# esp32-wroom-32.net
KiCad netlist of a schematic drawn in Altium Designer
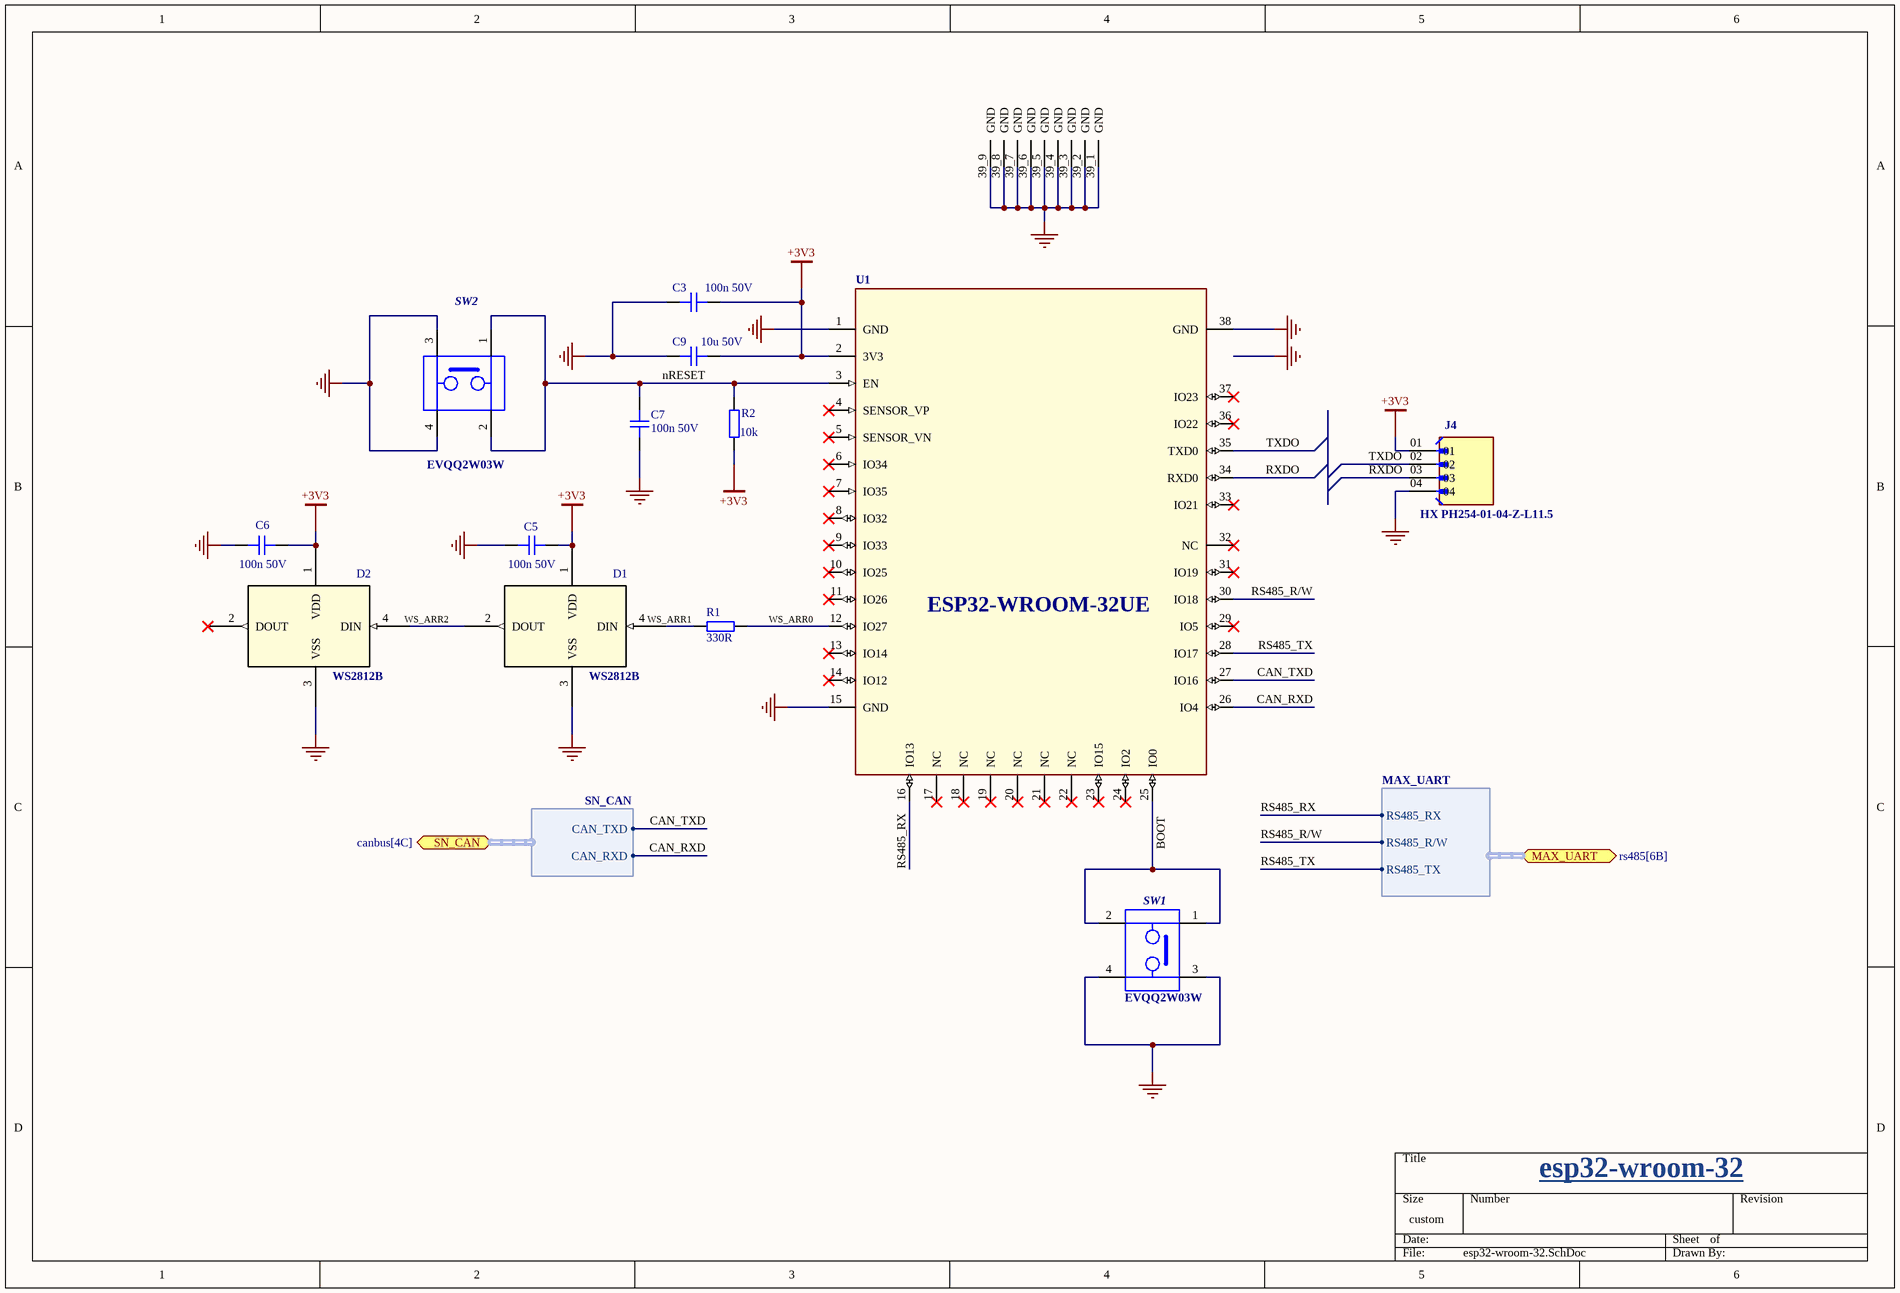
[diagram p0: esp32-wroom-32.SchDoc]

(export (version "E")
  (design (tool "Eeschema 10.0.6"))
  (components
    (comp (ref "C3")
      (value "100n 50V")
      (footprint "CAP_0603")
      (description "Capacitor SMD 0603")
      (libsource (lib "Sch_Lib") (part "CAP_0603"))
    )
    (comp (ref "C5")
      (value "100n 50V")
      (footprint "CAP_0603")
      (description "Capacitor SMD 0603")
      (libsource (lib "Sch_Lib") (part "CAP_0603"))
    )
    (comp (ref "C6")
      (value "100n 50V")
      (footprint "CAP_0603")
      (description "Capacitor SMD 0603")
      (libsource (lib "Sch_Lib") (part "CAP_0603"))
    )
    (comp (ref "C7")
      (value "100n 50V")
      (footprint "CAP_0805")
      (description "Capacitor SMD 0805")
      (libsource (lib "Sch_Lib") (part "CAP_0805"))
    )
    (comp (ref "C9")
      (value "10u 50V")
      (footprint "CAP_0603")
      (description "Capacitor SMD 0603")
      (libsource (lib "Sch_Lib") (part "CAP_0603"))
    )
    (comp (ref "D1")
      (value "WS2812B")
      (footprint "WS2812B_WDS")
      (description "Description")
      (fields (field (name "COPYRIGHT") "Copyright (C) 2026 Ultra Librarian. All rights reserved."))
      (libsource (lib "Sch_Lib") (part "WS2812B"))
    )
    (comp (ref "D2")
      (value "WS2812B")
      (footprint "WS2812B_WDS")
      (description "Description")
      (fields (field (name "COPYRIGHT") "Copyright (C) 2026 Ultra Librarian. All rights reserved."))
      (libsource (lib "Sch_Lib") (part "WS2812B"))
    )
    (comp (ref "J4")
      (value "HX PH254-01-04-Z-L11.5")
      (footprint "SAMTEC_TSW-104-08-T-S-LL")
      (fields (field (name "MF") "Samtec") (field (name "MP") "TSW-104-08-T-S-LL"))
      (libsource (lib "Sch_Lib") (part "4PIN_TSW-104-08-T-S-LL"))
    )
    (comp (ref "R1")
      (value "330R")
      (footprint "RES_0805")
      (description "Resistor SMD 0805")
      (libsource (lib "Sch_Lib") (part "RES_0805"))
    )
    (comp (ref "R2")
      (value "10k")
      (footprint "RES_0805")
      (description "Resistor SMD 0805")
      (libsource (lib "Sch_Lib") (part "RES_0805"))
    )
    (comp (ref "SW1")
      (value "EVQQ2W03W")
      (footprint "EVQQ2W03W")
      (description "White Push Plate Tactile Switch, SPST-NO 20 mA 3.1mm")
      (fields (field (name "MF") "Panasonic"))
      (libsource (lib "Sch_Lib") (part "EVQQ2W03W"))
    )
    (comp (ref "SW2")
      (value "EVQQ2W03W")
      (footprint "EVQQ2W03W")
      (description "White Push Plate Tactile Switch, SPST-NO 20 mA 3.1mm")
      (fields (field (name "MF") "Panasonic"))
      (libsource (lib "Sch_Lib") (part "EVQQ2W03W"))
    )
    (comp (ref "U1")
      (value "ESP32-WROOM-32UE")
      (footprint "MODULE_ESP32-WROOM-32UE(M113EH6400UH3Q0)")
      (fields (field (name "MF") "Espressif Systems") (field (name "MP") "ESP32-WROOM-32UE(M113EH6400UH3Q0)"))
      (libsource (lib "Sch_Lib") (part "ESP32-WROOM-32UE(M113EH6400UH3Q0)"))
    )
  )
  (nets
    (net (code "3") (name "+3V3") (class "Default")
      (node (ref "C3") (pin "2") (pinfunction "2_2") (pintype "passive"))
      (node (ref "C5") (pin "2") (pinfunction "2_2") (pintype "passive"))
      (node (ref "C6") (pin "2") (pinfunction "2_2") (pintype "passive"))
      (node (ref "C9") (pin "2") (pinfunction "2_2") (pintype "passive"))
      (node (ref "D1") (pin "1") (pinfunction "VDD_1") (pintype "power_in"))
      (node (ref "D2") (pin "1") (pinfunction "VDD_1") (pintype "power_in"))
      (node (ref "J4") (pin "01") (pinfunction "01_01") (pintype "passive"))
      (node (ref "R2") (pin "1") (pinfunction "1_1") (pintype "passive"))
      (node (ref "U1") (pin "2") (pinfunction "3V3_2") (pintype "power_in"))
    )
    (net (code "4") (name "/BOOT") (class "Default")
      (node (ref "SW1") (pin "1") (pinfunction "1_1") (pintype "passive"))
      (node (ref "SW1") (pin "2") (pinfunction "2_2") (pintype "passive"))
      (node (ref "U1") (pin "25") (pinfunction "IO0_25") (pintype "bidirectional"))
    )
    (net (code "5") (name "/CAN_RXD") (class "Default")
      (node (ref "U1") (pin "26") (pinfunction "IO4_26") (pintype "bidirectional"))
    )
    (net (code "6") (name "/CAN_TXD") (class "Default")
      (node (ref "U1") (pin "27") (pinfunction "IO16_27") (pintype "bidirectional"))
    )
    (net (code "7") (name "/RS485_RX") (class "Default")
      (node (ref "U1") (pin "16") (pinfunction "IO13_16") (pintype "bidirectional"))
    )
    (net (code "8") (name "/RS485_R{slash}W") (class "Default")
      (node (ref "U1") (pin "30") (pinfunction "IO18_30") (pintype "bidirectional"))
    )
    (net (code "9") (name "/RS485_TX") (class "Default")
      (node (ref "U1") (pin "28") (pinfunction "IO17_28") (pintype "bidirectional"))
    )
    (net (code "10") (name "/RXDO") (class "Default")
      (node (ref "J4") (pin "03") (pinfunction "03_03") (pintype "passive"))
      (node (ref "U1") (pin "34") (pinfunction "RXD0_34") (pintype "bidirectional"))
    )
    (net (code "11") (name "/TXDO") (class "Default")
      (node (ref "J4") (pin "02") (pinfunction "02_02") (pintype "passive"))
      (node (ref "U1") (pin "35") (pinfunction "TXD0_35") (pintype "bidirectional"))
    )
    (net (code "12") (name "/WS_ARR0") (class "Default")
      (node (ref "R1") (pin "1") (pinfunction "1_1") (pintype "passive"))
      (node (ref "U1") (pin "12") (pinfunction "IO27_12") (pintype "bidirectional"))
    )
    (net (code "13") (name "/WS_ARR1") (class "Default")
      (node (ref "D1") (pin "4") (pinfunction "DIN_4") (pintype "input"))
      (node (ref "R1") (pin "2") (pinfunction "2_2") (pintype "passive"))
    )
    (net (code "14") (name "/WS_ARR2") (class "Default")
      (node (ref "D1") (pin "2") (pinfunction "DOUT_2") (pintype "output"))
      (node (ref "D2") (pin "4") (pinfunction "DIN_4") (pintype "input"))
    )
    (net (code "15") (name "/nRESET") (class "Default")
      (node (ref "C7") (pin "2") (pinfunction "2_2") (pintype "passive"))
      (node (ref "R2") (pin "2") (pinfunction "2_2") (pintype "passive"))
      (node (ref "SW2") (pin "1") (pinfunction "1_1") (pintype "passive"))
      (node (ref "SW2") (pin "2") (pinfunction "2_2") (pintype "passive"))
      (node (ref "U1") (pin "3") (pinfunction "EN_3") (pintype "input"))
    )
    (net (code "18") (name "GND") (class "Default")
      (node (ref "C3") (pin "1") (pinfunction "1_1") (pintype "passive"))
      (node (ref "C5") (pin "1") (pinfunction "1_1") (pintype "passive"))
      (node (ref "C6") (pin "1") (pinfunction "1_1") (pintype "passive"))
      (node (ref "C7") (pin "1") (pinfunction "1_1") (pintype "passive"))
      (node (ref "C9") (pin "1") (pinfunction "1_1") (pintype "passive"))
      (node (ref "D1") (pin "3") (pinfunction "VSS_3") (pintype "power_in"))
      (node (ref "D2") (pin "3") (pinfunction "VSS_3") (pintype "power_in"))
      (node (ref "J4") (pin "04") (pinfunction "04_04") (pintype "passive"))
      (node (ref "SW1") (pin "3") (pinfunction "3_3") (pintype "passive"))
      (node (ref "SW1") (pin "4") (pinfunction "4_4") (pintype "passive"))
      (node (ref "SW2") (pin "3") (pinfunction "3_3") (pintype "passive"))
      (node (ref "SW2") (pin "4") (pinfunction "4_4") (pintype "passive"))
      (node (ref "U1") (pin "1") (pinfunction "GND_1") (pintype "power_in"))
      (node (ref "U1") (pin "15") (pinfunction "GND_15") (pintype "power_in"))
      (node (ref "U1") (pin "38") (pinfunction "GND_38") (pintype "power_in"))
      (node (ref "U1") (pin "39_1") (pinfunction "GND_39_1") (pintype "power_in"))
      (node (ref "U1") (pin "39_2") (pinfunction "GND_39_2") (pintype "power_in"))
      (node (ref "U1") (pin "39_3") (pinfunction "GND_39_3") (pintype "power_in"))
      (node (ref "U1") (pin "39_4") (pinfunction "GND_39_4") (pintype "power_in"))
      (node (ref "U1") (pin "39_5") (pinfunction "GND_39_5") (pintype "power_in"))
      (node (ref "U1") (pin "39_6") (pinfunction "GND_39_6") (pintype "power_in"))
      (node (ref "U1") (pin "39_7") (pinfunction "GND_39_7") (pintype "power_in"))
      (node (ref "U1") (pin "39_8") (pinfunction "GND_39_8") (pintype "power_in"))
      (node (ref "U1") (pin "39_9") (pinfunction "GND_39_9") (pintype "power_in"))
    )
    (net (code "19") (name "unconnected-(D2-DOUT-Pad2)") (class "Default")
      (node (ref "D2") (pin "2") (pinfunction "DOUT_2") (pintype "output+no_connect"))
    )
    (net (code "20") (name "unconnected-(U1-IO2-Pad24)") (class "Default")
      (node (ref "U1") (pin "24") (pinfunction "IO2_24") (pintype "bidirectional+no_connect"))
    )
    (net (code "21") (name "unconnected-(U1-IO5-Pad29)") (class "Default")
      (node (ref "U1") (pin "29") (pinfunction "IO5_29") (pintype "bidirectional+no_connect"))
    )
    (net (code "22") (name "unconnected-(U1-IO12-Pad14)") (class "Default")
      (node (ref "U1") (pin "14") (pinfunction "IO12_14") (pintype "bidirectional+no_connect"))
    )
    (net (code "23") (name "unconnected-(U1-IO14-Pad13)") (class "Default")
      (node (ref "U1") (pin "13") (pinfunction "IO14_13") (pintype "bidirectional+no_connect"))
    )
    (net (code "24") (name "unconnected-(U1-IO15-Pad23)") (class "Default")
      (node (ref "U1") (pin "23") (pinfunction "IO15_23") (pintype "bidirectional+no_connect"))
    )
    (net (code "25") (name "unconnected-(U1-IO19-Pad31)") (class "Default")
      (node (ref "U1") (pin "31") (pinfunction "IO19_31") (pintype "bidirectional+no_connect"))
    )
    (net (code "26") (name "unconnected-(U1-IO21-Pad33)") (class "Default")
      (node (ref "U1") (pin "33") (pinfunction "IO21_33") (pintype "bidirectional+no_connect"))
    )
    (net (code "27") (name "unconnected-(U1-IO22-Pad36)") (class "Default")
      (node (ref "U1") (pin "36") (pinfunction "IO22_36") (pintype "bidirectional+no_connect"))
    )
    (net (code "28") (name "unconnected-(U1-IO23-Pad37)") (class "Default")
      (node (ref "U1") (pin "37") (pinfunction "IO23_37") (pintype "bidirectional+no_connect"))
    )
    (net (code "29") (name "unconnected-(U1-IO25-Pad10)") (class "Default")
      (node (ref "U1") (pin "10") (pinfunction "IO25_10") (pintype "bidirectional+no_connect"))
    )
    (net (code "30") (name "unconnected-(U1-IO26-Pad11)") (class "Default")
      (node (ref "U1") (pin "11") (pinfunction "IO26_11") (pintype "bidirectional+no_connect"))
    )
    (net (code "31") (name "unconnected-(U1-IO32-Pad8)") (class "Default")
      (node (ref "U1") (pin "8") (pinfunction "IO32_8") (pintype "bidirectional+no_connect"))
    )
    (net (code "32") (name "unconnected-(U1-IO33-Pad9)") (class "Default")
      (node (ref "U1") (pin "9") (pinfunction "IO33_9") (pintype "bidirectional+no_connect"))
    )
    (net (code "33") (name "unconnected-(U1-IO34-Pad6)") (class "Default")
      (node (ref "U1") (pin "6") (pinfunction "IO34_6") (pintype "input+no_connect"))
    )
    (net (code "34") (name "unconnected-(U1-IO35-Pad7)") (class "Default")
      (node (ref "U1") (pin "7") (pinfunction "IO35_7") (pintype "input+no_connect"))
    )
    (net (code "35") (name "unconnected-(U1-NC-Pad17)") (class "Default")
      (node (ref "U1") (pin "17") (pinfunction "NC_17") (pintype "passive+no_connect"))
    )
    (net (code "36") (name "unconnected-(U1-NC-Pad18)") (class "Default")
      (node (ref "U1") (pin "18") (pinfunction "NC_18") (pintype "passive+no_connect"))
    )
    (net (code "37") (name "unconnected-(U1-NC-Pad19)") (class "Default")
      (node (ref "U1") (pin "19") (pinfunction "NC_19") (pintype "passive+no_connect"))
    )
    (net (code "38") (name "unconnected-(U1-NC-Pad20)") (class "Default")
      (node (ref "U1") (pin "20") (pinfunction "NC_20") (pintype "passive+no_connect"))
    )
    (net (code "39") (name "unconnected-(U1-NC-Pad21)") (class "Default")
      (node (ref "U1") (pin "21") (pinfunction "NC_21") (pintype "passive+no_connect"))
    )
    (net (code "40") (name "unconnected-(U1-NC-Pad22)") (class "Default")
      (node (ref "U1") (pin "22") (pinfunction "NC_22") (pintype "passive+no_connect"))
    )
    (net (code "41") (name "unconnected-(U1-NC-Pad32)") (class "Default")
      (node (ref "U1") (pin "32") (pinfunction "NC_32") (pintype "passive+no_connect"))
    )
    (net (code "42") (name "unconnected-(U1-SENSOR_VN-Pad5)") (class "Default")
      (node (ref "U1") (pin "5") (pinfunction "SENSOR_VN_5") (pintype "input+no_connect"))
    )
    (net (code "43") (name "unconnected-(U1-SENSOR_VP-Pad4)") (class "Default")
      (node (ref "U1") (pin "4") (pinfunction "SENSOR_VP_4") (pintype "input+no_connect"))
    )
  )
)
